# untitled.net
KiCad netlist of a schematic drawn in EAGLE
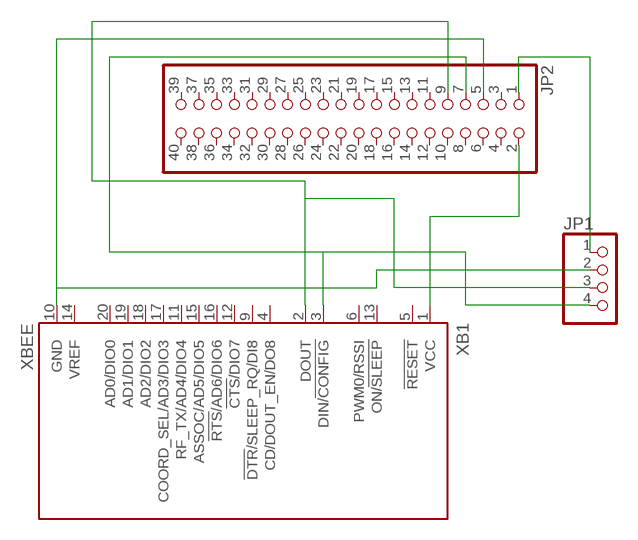
[diagram p0: schematic, sheet 1]

(export (version "E")
  (design (tool "Eeschema 10.0.6"))
  (components
    (comp (ref "JP1")
      (value "PINHD-1X4")
      (footprint "eagle-import:1X04")
      (libsource (lib "eagle-import") (part "PINHD-1X4"))
    )
    (comp (ref "JP2")
      (value "PINHD-2X20")
      (footprint "eagle-import:2X20")
      (libsource (lib "eagle-import") (part "PINHD-2X20"))
    )
    (comp (ref "XB1")
      (value "XBEE")
      (footprint "eagle-import:XBEE")
      (fields (field (name "MPN") "XBP24-Z7UIT-004"))
      (libsource (lib "eagle-import") (part "XBEE"))
    )
  )
  (nets
    (net (code "1") (name "Net-(JP1-Pad1)") (class "Default")
      (node (ref "JP1") (pin "1") (pinfunction "1_1") (pintype "passive"))
      (node (ref "JP2") (pin "1") (pinfunction "1_1") (pintype "passive"))
    )
    (net (code "2") (name "Net-(XB1-DIN{slash}~{CONFIG})") (class "Default")
      (node (ref "JP1") (pin "4") (pinfunction "4_4") (pintype "passive"))
      (node (ref "JP2") (pin "7") (pinfunction "7_7") (pintype "passive"))
      (node (ref "XB1") (pin "3") (pinfunction "DIN/~{CONFIG}_3") (pintype "input"))
    )
    (net (code "3") (name "Net-(XB1-DOUT)") (class "Default")
      (node (ref "JP1") (pin "3") (pinfunction "3_3") (pintype "passive"))
      (node (ref "JP2") (pin "9") (pinfunction "9_9") (pintype "passive"))
      (node (ref "XB1") (pin "2") (pinfunction "DOUT_2") (pintype "output"))
    )
    (net (code "4") (name "Net-(XB1-GND)") (class "Default")
      (node (ref "JP1") (pin "2") (pinfunction "2_2") (pintype "passive"))
      (node (ref "JP2") (pin "5") (pinfunction "5_5") (pintype "passive"))
      (node (ref "XB1") (pin "10") (pinfunction "GND_10") (pintype "power_in"))
    )
    (net (code "5") (name "Net-(XB1-VCC)") (class "Default")
      (node (ref "JP2") (pin "2") (pinfunction "2_2") (pintype "passive"))
      (node (ref "XB1") (pin "1") (pinfunction "VCC_1") (pintype "power_in"))
    )
    (net (code "6") (name "unconnected-(JP2-Pad3)") (class "Default")
      (node (ref "JP2") (pin "3") (pinfunction "3_3") (pintype "passive"))
    )
    (net (code "7") (name "unconnected-(JP2-Pad4)") (class "Default")
      (node (ref "JP2") (pin "4") (pinfunction "4_4") (pintype "passive"))
    )
    (net (code "8") (name "unconnected-(JP2-Pad6)") (class "Default")
      (node (ref "JP2") (pin "6") (pinfunction "6_6") (pintype "passive"))
    )
    (net (code "9") (name "unconnected-(JP2-Pad8)") (class "Default")
      (node (ref "JP2") (pin "8") (pinfunction "8_8") (pintype "passive"))
    )
    (net (code "10") (name "unconnected-(JP2-Pad10)") (class "Default")
      (node (ref "JP2") (pin "10") (pinfunction "10_10") (pintype "passive"))
    )
    (net (code "11") (name "unconnected-(JP2-Pad11)") (class "Default")
      (node (ref "JP2") (pin "11") (pinfunction "11_11") (pintype "passive"))
    )
    (net (code "12") (name "unconnected-(JP2-Pad12)") (class "Default")
      (node (ref "JP2") (pin "12") (pinfunction "12_12") (pintype "passive"))
    )
    (net (code "13") (name "unconnected-(JP2-Pad13)") (class "Default")
      (node (ref "JP2") (pin "13") (pinfunction "13_13") (pintype "passive"))
    )
    (net (code "14") (name "unconnected-(JP2-Pad14)") (class "Default")
      (node (ref "JP2") (pin "14") (pinfunction "14_14") (pintype "passive"))
    )
    (net (code "15") (name "unconnected-(JP2-Pad15)") (class "Default")
      (node (ref "JP2") (pin "15") (pinfunction "15_15") (pintype "passive"))
    )
    (net (code "16") (name "unconnected-(JP2-Pad16)") (class "Default")
      (node (ref "JP2") (pin "16") (pinfunction "16_16") (pintype "passive"))
    )
    (net (code "17") (name "unconnected-(JP2-Pad17)") (class "Default")
      (node (ref "JP2") (pin "17") (pinfunction "17_17") (pintype "passive"))
    )
    (net (code "18") (name "unconnected-(JP2-Pad18)") (class "Default")
      (node (ref "JP2") (pin "18") (pinfunction "18_18") (pintype "passive"))
    )
    (net (code "19") (name "unconnected-(JP2-Pad19)") (class "Default")
      (node (ref "JP2") (pin "19") (pinfunction "19_19") (pintype "passive"))
    )
    (net (code "20") (name "unconnected-(JP2-Pad20)") (class "Default")
      (node (ref "JP2") (pin "20") (pinfunction "20_20") (pintype "passive"))
    )
    (net (code "21") (name "unconnected-(JP2-Pad21)") (class "Default")
      (node (ref "JP2") (pin "21") (pinfunction "21_21") (pintype "passive"))
    )
    (net (code "22") (name "unconnected-(JP2-Pad22)") (class "Default")
      (node (ref "JP2") (pin "22") (pinfunction "22_22") (pintype "passive"))
    )
    (net (code "23") (name "unconnected-(JP2-Pad23)") (class "Default")
      (node (ref "JP2") (pin "23") (pinfunction "23_23") (pintype "passive"))
    )
    (net (code "24") (name "unconnected-(JP2-Pad24)") (class "Default")
      (node (ref "JP2") (pin "24") (pinfunction "24_24") (pintype "passive"))
    )
    (net (code "25") (name "unconnected-(JP2-Pad25)") (class "Default")
      (node (ref "JP2") (pin "25") (pinfunction "25_25") (pintype "passive"))
    )
    (net (code "26") (name "unconnected-(JP2-Pad26)") (class "Default")
      (node (ref "JP2") (pin "26") (pinfunction "26_26") (pintype "passive"))
    )
    (net (code "27") (name "unconnected-(JP2-Pad27)") (class "Default")
      (node (ref "JP2") (pin "27") (pinfunction "27_27") (pintype "passive"))
    )
    (net (code "28") (name "unconnected-(JP2-Pad28)") (class "Default")
      (node (ref "JP2") (pin "28") (pinfunction "28_28") (pintype "passive"))
    )
    (net (code "29") (name "unconnected-(JP2-Pad29)") (class "Default")
      (node (ref "JP2") (pin "29") (pinfunction "29_29") (pintype "passive"))
    )
    (net (code "30") (name "unconnected-(JP2-Pad30)") (class "Default")
      (node (ref "JP2") (pin "30") (pinfunction "30_30") (pintype "passive"))
    )
    (net (code "31") (name "unconnected-(JP2-Pad31)") (class "Default")
      (node (ref "JP2") (pin "31") (pinfunction "31_31") (pintype "passive"))
    )
    (net (code "32") (name "unconnected-(JP2-Pad32)") (class "Default")
      (node (ref "JP2") (pin "32") (pinfunction "32_32") (pintype "passive"))
    )
    (net (code "33") (name "unconnected-(JP2-Pad33)") (class "Default")
      (node (ref "JP2") (pin "33") (pinfunction "33_33") (pintype "passive"))
    )
    (net (code "34") (name "unconnected-(JP2-Pad34)") (class "Default")
      (node (ref "JP2") (pin "34") (pinfunction "34_34") (pintype "passive"))
    )
    (net (code "35") (name "unconnected-(JP2-Pad35)") (class "Default")
      (node (ref "JP2") (pin "35") (pinfunction "35_35") (pintype "passive"))
    )
    (net (code "36") (name "unconnected-(JP2-Pad36)") (class "Default")
      (node (ref "JP2") (pin "36") (pinfunction "36_36") (pintype "passive"))
    )
    (net (code "37") (name "unconnected-(JP2-Pad37)") (class "Default")
      (node (ref "JP2") (pin "37") (pinfunction "37_37") (pintype "passive"))
    )
    (net (code "38") (name "unconnected-(JP2-Pad38)") (class "Default")
      (node (ref "JP2") (pin "38") (pinfunction "38_38") (pintype "passive"))
    )
    (net (code "39") (name "unconnected-(JP2-Pad39)") (class "Default")
      (node (ref "JP2") (pin "39") (pinfunction "39_39") (pintype "passive"))
    )
    (net (code "40") (name "unconnected-(JP2-Pad40)") (class "Default")
      (node (ref "JP2") (pin "40") (pinfunction "40_40") (pintype "passive"))
    )
    (net (code "41") (name "unconnected-(XB1-AD0{slash}DIO0-Pad20)") (class "Default")
      (node (ref "XB1") (pin "20") (pinfunction "AD0/DIO0_20") (pintype "bidirectional"))
    )
    (net (code "42") (name "unconnected-(XB1-AD1{slash}DIO1-Pad19)") (class "Default")
      (node (ref "XB1") (pin "19") (pinfunction "AD1/DIO1_19") (pintype "bidirectional"))
    )
    (net (code "43") (name "unconnected-(XB1-AD2{slash}DIO2-Pad18)") (class "Default")
      (node (ref "XB1") (pin "18") (pinfunction "AD2/DIO2_18") (pintype "bidirectional"))
    )
    (net (code "44") (name "unconnected-(XB1-ASSOC{slash}AD5{slash}DIO5-Pad15)") (class "Default")
      (node (ref "XB1") (pin "15") (pinfunction "ASSOC/AD5/DIO5_15") (pintype "bidirectional"))
    )
    (net (code "45") (name "unconnected-(XB1-CD{slash}DOUT_EN{slash}DO8-Pad4)") (class "Default")
      (node (ref "XB1") (pin "4") (pinfunction "CD/DOUT_EN/DO8_4") (pintype "output"))
    )
    (net (code "46") (name "unconnected-(XB1-COORD_SEL{slash}AD3{slash}DIO3-Pad17)") (class "Default")
      (node (ref "XB1") (pin "17") (pinfunction "COORD_SEL/AD3/DIO3_17") (pintype "bidirectional"))
    )
    (net (code "47") (name "unconnected-(XB1-ON{slash}~{SLEEP}-Pad13)") (class "Default")
      (node (ref "XB1") (pin "13") (pinfunction "ON/~{SLEEP}_13") (pintype "output"))
    )
    (net (code "48") (name "unconnected-(XB1-PWM0{slash}RSSI-Pad6)") (class "Default")
      (node (ref "XB1") (pin "6") (pinfunction "PWM0/RSSI_6") (pintype "output"))
    )
    (net (code "49") (name "unconnected-(XB1-RF_TX{slash}AD4{slash}DIO4-Pad11)") (class "Default")
      (node (ref "XB1") (pin "11") (pinfunction "RF_TX/AD4/DIO4_11") (pintype "bidirectional"))
    )
    (net (code "50") (name "unconnected-(XB1-VREF-Pad14)") (class "Default")
      (node (ref "XB1") (pin "14") (pinfunction "VREF_14") (pintype "input"))
    )
    (net (code "51") (name "unconnected-(XB1-~{CTS}{slash}DIO7-Pad12)") (class "Default")
      (node (ref "XB1") (pin "12") (pinfunction "~{CTS}/DIO7_12") (pintype "bidirectional"))
    )
    (net (code "52") (name "unconnected-(XB1-~{DTR}{slash}SLEEP_RQ{slash}DI8-Pad9)") (class "Default")
      (node (ref "XB1") (pin "9") (pinfunction "~{DTR}/SLEEP_RQ/DI8_9") (pintype "bidirectional"))
    )
    (net (code "53") (name "unconnected-(XB1-~{RESET}-Pad5)") (class "Default")
      (node (ref "XB1") (pin "5") (pinfunction "~{RESET}_5") (pintype "input"))
    )
    (net (code "54") (name "unconnected-(XB1-~{RTS}{slash}AD6{slash}DIO6-Pad16)") (class "Default")
      (node (ref "XB1") (pin "16") (pinfunction "~{RTS}/AD6/DIO6_16") (pintype "bidirectional"))
    )
  )
)
